# Power_MCU.net
KiCad netlist of a schematic drawn in Altium Designer
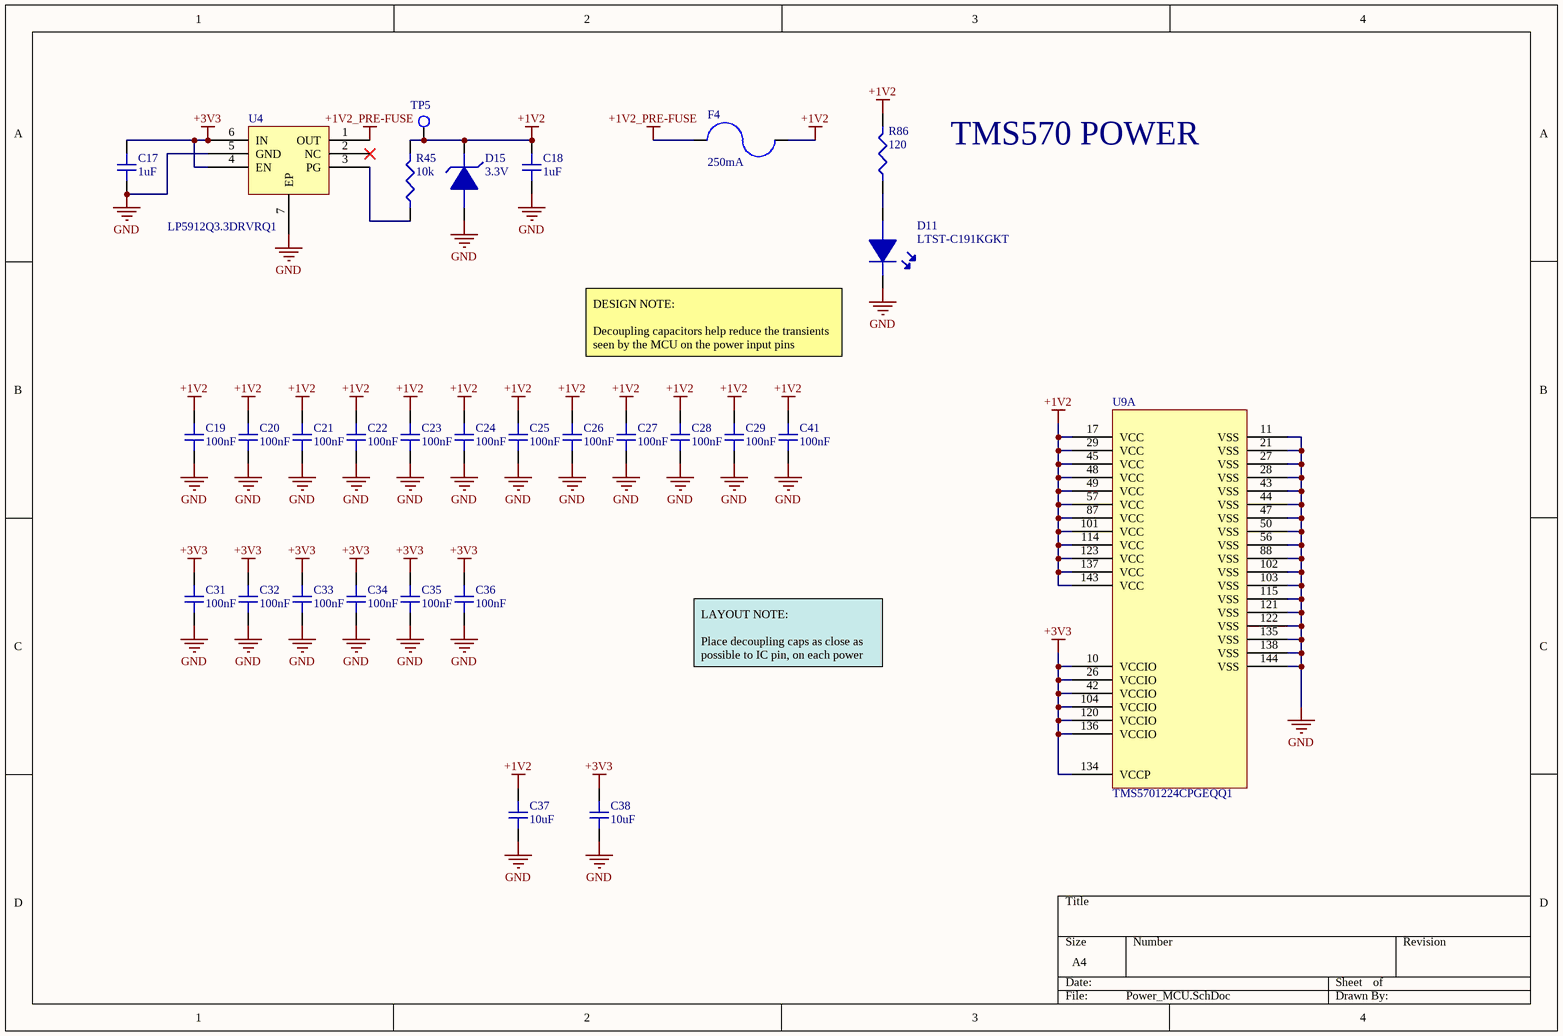
[diagram p0: Power_MCU.SchDoc]

(export (version "E")
  (design (tool "Eeschema 10.0.6"))
  (components
    (comp (ref "C17")
      (value "1uF")
      (footprint "C0805")
      (description "CAP CER 1UF 10V X7R 0805")
      (fields
        (field (name "MANUFACTURER") "Kyocera AVX")
        (field (name "MANUFACTURER PART NUMBER") "0805ZC105KAT2A")
      )
      (libsource (lib "PHANTOM_LIBRARY") (part "0805ZC105KAT2A"))
    )
    (comp (ref "C18")
      (value "1uF")
      (footprint "C0805")
      (description "CAP CER 1UF 10V X7R 0805")
      (fields
        (field (name "MANUFACTURER") "Kyocera AVX")
        (field (name "MANUFACTURER PART NUMBER") "0805ZC105KAT2A")
      )
      (libsource (lib "PHANTOM_LIBRARY") (part "0805ZC105KAT2A"))
    )
    (comp (ref "C19")
      (value "100nF")
      (footprint "PHANTOM_FOOTPRINTS:C0805")
      (description "CAP MLCC 100nF 10Volts U2J 5%")
      (fields
        (field (name "MANUFACTURER") "Murata")
        (field (name "MANUFACTURER PART NUMBER") "GRM21B7U1A104JA01L")
      )
      (libsource (lib "PHANTOM_LIBRARY") (part "GRM21B7U1A104JA01L"))
    )
    (comp (ref "C20")
      (value "100nF")
      (footprint "PHANTOM_FOOTPRINTS:C0805")
      (description "CAP MLCC 100nF 10Volts U2J 5%")
      (fields
        (field (name "MANUFACTURER") "Murata")
        (field (name "MANUFACTURER PART NUMBER") "GRM21B7U1A104JA01L")
      )
      (libsource (lib "PHANTOM_LIBRARY") (part "GRM21B7U1A104JA01L"))
    )
    (comp (ref "C21")
      (value "100nF")
      (footprint "PHANTOM_FOOTPRINTS:C0805")
      (description "CAP MLCC 100nF 10Volts U2J 5%")
      (fields
        (field (name "MANUFACTURER") "Murata")
        (field (name "MANUFACTURER PART NUMBER") "GRM21B7U1A104JA01L")
      )
      (libsource (lib "PHANTOM_LIBRARY") (part "GRM21B7U1A104JA01L"))
    )
    (comp (ref "C22")
      (value "100nF")
      (footprint "PHANTOM_FOOTPRINTS:C0805")
      (description "CAP MLCC 100nF 10Volts U2J 5%")
      (fields
        (field (name "MANUFACTURER") "Murata")
        (field (name "MANUFACTURER PART NUMBER") "GRM21B7U1A104JA01L")
      )
      (libsource (lib "PHANTOM_LIBRARY") (part "GRM21B7U1A104JA01L"))
    )
    (comp (ref "C23")
      (value "100nF")
      (footprint "PHANTOM_FOOTPRINTS:C0805")
      (description "CAP MLCC 100nF 10Volts U2J 5%")
      (fields
        (field (name "MANUFACTURER") "Murata")
        (field (name "MANUFACTURER PART NUMBER") "GRM21B7U1A104JA01L")
      )
      (libsource (lib "PHANTOM_LIBRARY") (part "GRM21B7U1A104JA01L"))
    )
    (comp (ref "C24")
      (value "100nF")
      (footprint "PHANTOM_FOOTPRINTS:C0805")
      (description "CAP MLCC 100nF 10Volts U2J 5%")
      (fields
        (field (name "MANUFACTURER") "Murata")
        (field (name "MANUFACTURER PART NUMBER") "GRM21B7U1A104JA01L")
      )
      (libsource (lib "PHANTOM_LIBRARY") (part "GRM21B7U1A104JA01L"))
    )
    (comp (ref "C25")
      (value "100nF")
      (footprint "PHANTOM_FOOTPRINTS:C0805")
      (description "CAP MLCC 100nF 10Volts U2J 5%")
      (fields
        (field (name "MANUFACTURER") "Murata")
        (field (name "MANUFACTURER PART NUMBER") "GRM21B7U1A104JA01L")
      )
      (libsource (lib "PHANTOM_LIBRARY") (part "GRM21B7U1A104JA01L"))
    )
    (comp (ref "C26")
      (value "100nF")
      (footprint "PHANTOM_FOOTPRINTS:C0805")
      (description "CAP MLCC 100nF 10Volts U2J 5%")
      (fields
        (field (name "MANUFACTURER") "Murata")
        (field (name "MANUFACTURER PART NUMBER") "GRM21B7U1A104JA01L")
      )
      (libsource (lib "PHANTOM_LIBRARY") (part "GRM21B7U1A104JA01L"))
    )
    (comp (ref "C27")
      (value "100nF")
      (footprint "PHANTOM_FOOTPRINTS:C0805")
      (description "CAP MLCC 100nF 10Volts U2J 5%")
      (fields
        (field (name "MANUFACTURER") "Murata")
        (field (name "MANUFACTURER PART NUMBER") "GRM21B7U1A104JA01L")
      )
      (libsource (lib "PHANTOM_LIBRARY") (part "GRM21B7U1A104JA01L"))
    )
    (comp (ref "C28")
      (value "100nF")
      (footprint "PHANTOM_FOOTPRINTS:C0805")
      (description "CAP MLCC 100nF 10Volts U2J 5%")
      (fields
        (field (name "MANUFACTURER") "Murata")
        (field (name "MANUFACTURER PART NUMBER") "GRM21B7U1A104JA01L")
      )
      (libsource (lib "PHANTOM_LIBRARY") (part "GRM21B7U1A104JA01L"))
    )
    (comp (ref "C29")
      (value "100nF")
      (footprint "PHANTOM_FOOTPRINTS:C0805")
      (description "CAP MLCC 100nF 10Volts U2J 5%")
      (fields
        (field (name "MANUFACTURER") "Murata")
        (field (name "MANUFACTURER PART NUMBER") "GRM21B7U1A104JA01L")
      )
      (libsource (lib "PHANTOM_LIBRARY") (part "GRM21B7U1A104JA01L"))
    )
    (comp (ref "C31")
      (value "100nF")
      (footprint "PHANTOM_FOOTPRINTS:C0805")
      (description "CAP MLCC 100nF 10Volts U2J 5%")
      (fields
        (field (name "MANUFACTURER") "Murata")
        (field (name "MANUFACTURER PART NUMBER") "GRM21B7U1A104JA01L")
      )
      (libsource (lib "PHANTOM_LIBRARY") (part "GRM21B7U1A104JA01L"))
    )
    (comp (ref "C32")
      (value "100nF")
      (footprint "PHANTOM_FOOTPRINTS:C0805")
      (description "CAP MLCC 100nF 10Volts U2J 5%")
      (fields
        (field (name "MANUFACTURER") "Murata")
        (field (name "MANUFACTURER PART NUMBER") "GRM21B7U1A104JA01L")
      )
      (libsource (lib "PHANTOM_LIBRARY") (part "GRM21B7U1A104JA01L"))
    )
    (comp (ref "C33")
      (value "100nF")
      (footprint "PHANTOM_FOOTPRINTS:C0805")
      (description "CAP MLCC 100nF 10Volts U2J 5%")
      (fields
        (field (name "MANUFACTURER") "Murata")
        (field (name "MANUFACTURER PART NUMBER") "GRM21B7U1A104JA01L")
      )
      (libsource (lib "PHANTOM_LIBRARY") (part "GRM21B7U1A104JA01L"))
    )
    (comp (ref "C34")
      (value "100nF")
      (footprint "PHANTOM_FOOTPRINTS:C0805")
      (description "CAP MLCC 100nF 10Volts U2J 5%")
      (fields
        (field (name "MANUFACTURER") "Murata")
        (field (name "MANUFACTURER PART NUMBER") "GRM21B7U1A104JA01L")
      )
      (libsource (lib "PHANTOM_LIBRARY") (part "GRM21B7U1A104JA01L"))
    )
    (comp (ref "C35")
      (value "100nF")
      (footprint "PHANTOM_FOOTPRINTS:C0805")
      (description "CAP MLCC 100nF 10Volts U2J 5%")
      (fields
        (field (name "MANUFACTURER") "Murata")
        (field (name "MANUFACTURER PART NUMBER") "GRM21B7U1A104JA01L")
      )
      (libsource (lib "PHANTOM_LIBRARY") (part "GRM21B7U1A104JA01L"))
    )
    (comp (ref "C36")
      (value "100nF")
      (footprint "PHANTOM_FOOTPRINTS:C0805")
      (description "CAP MLCC 100nF 10Volts U2J 5%")
      (fields
        (field (name "MANUFACTURER") "Murata")
        (field (name "MANUFACTURER PART NUMBER") "GRM21B7U1A104JA01L")
      )
      (libsource (lib "PHANTOM_LIBRARY") (part "GRM21B7U1A104JA01L"))
    )
    (comp (ref "C37")
      (value "10uF")
      (footprint "TANT_10u")
      (fields
        (field (name "MANUFACTURER") "Kyocera AVX")
        (field (name "MANUFACTURER PART NUMBER") "F381A106MMA")
        (field (name "TOLERANCE") "20%")
      )
      (libsource (lib "PHANTOM_LIBRARY") (part "F381A106MMA"))
    )
    (comp (ref "C38")
      (value "10uF")
      (footprint "TANT_10u")
      (fields
        (field (name "MANUFACTURER") "Kyocera AVX")
        (field (name "MANUFACTURER PART NUMBER") "F381A106MMA")
        (field (name "TOLERANCE") "20%")
      )
      (libsource (lib "PHANTOM_LIBRARY") (part "F381A106MMA"))
    )
    (comp (ref "C41")
      (value "100nF")
      (footprint "PHANTOM_FOOTPRINTS:C0805")
      (description "CAP MLCC 100nF 10Volts U2J 5%")
      (fields
        (field (name "MANUFACTURER") "Murata")
        (field (name "MANUFACTURER PART NUMBER") "GRM21B7U1A104JA01L")
      )
      (libsource (lib "PHANTOM_LIBRARY") (part "GRM21B7U1A104JA01L"))
    )
    (comp (ref "D11")
      (value "LTST-C191KGKT")
      (footprint "LED_0603")
      (description "LED GREEN CLEAR 0603 SMD")
      (fields (field (name "MANUFACTURER") "Vishay Lite-On"))
      (libsource (lib "PHANTOM_LIBRARY") (part "LTST-C191KGKT"))
    )
    (comp (ref "D15")
      (value "3.3V")
      (footprint "DIODE_TVS")
      (description "DIODE ZENER 3.3V 1.5W SMA")
      (fields
        (field (name "MANUFACTURER") "ON Semiconductor")
        (field (name "MANUFACTURER PART NUMBER") "1SMA5913BT3G")
      )
      (libsource (lib "PHANTOM_LIBRARY") (part "1SMA5913BT3G"))
    )
    (comp (ref "F4")
      (value "250mA")
      (footprint "FUSE_0603")
      (description "FUSE_0.25A SMD 0603 BOARD MNT 250MA 32VAC 63VDC")
      (fields (field (name "MANUFACTURER") "Bel") (field (name "MANUFACTURER PART NUMBER") "C2Q250"))
      (libsource (lib "PHANTOM_LIBRARY") (part "C2Q250"))
    )
    (comp (ref "R45")
      (value "10k")
      (footprint "R0805")
      (description "RES SMD 10K OHM 1% 1/8W 0805")
      (fields
        (field (name "MANUFACTURER") "Yageo Phycomp")
        (field (name "MANUFACTURER PART NUMBER") "RC0805FR-071KL")
      )
      (libsource (lib "PHANTOM_LIBRARY") (part "RC0805FR-071KL"))
    )
    (comp (ref "R86")
      (value "120")
      (footprint "R0805")
      (description "RES SMD 120 OHM 1% 1/8W 0805")
      (fields
        (field (name "MANUFACTURER") "Yageo")
        (field (name "MANUFACTURER PART NUMBER") "RC0805FR-07120RL")
      )
      (libsource (lib "PHANTOM_LIBRARY") (part "RC0805FR-07120RL"))
    )
    (comp (ref "TP5")
      (value "5015")
      (footprint "TP_HOOK")
      (description "TEST POINT, PCB, SMT")
      (fields (field (name "MANUFACTURER") "Keystone Electronics"))
      (libsource (lib "PHANTOM_LIBRARY") (part "5015"))
    )
    (comp (ref "U4")
      (value "LP5912Q3.3DRVRQ1")
      (footprint "WSON")
      (description "LDO_1V2 REG 3.3V INPUT 1V2 OUTPUT 0.5A")
      (fields (field (name "MANUFACTURER") "Texas Instruments"))
      (libsource (lib "PHANTOM_LIBRARY") (part "LP5912Q3.3DRVRQ1"))
    )
    (comp (ref "U9")
      (value "TMS5701224CPGEQQ1")
      (footprint "LQFP-144")
      (description "ARM CORTEX R4 LOCK STEP HERCULES MCU")
      (fields (field (name "MANUFACTURER") "Texas Instruments"))
      (libsource (lib "PHANTOM_LIBRARY") (part "TMS5701224CPGEQQ1"))
    )
  )
  (nets
    (net (code "1") (name "+1V2") (class "Default")
      (node (ref "C18") (pin "2") (pinfunction "2_2") (pintype "passive"))
      (node (ref "C19") (pin "2") (pinfunction "2_2") (pintype "passive"))
      (node (ref "C20") (pin "2") (pinfunction "2_2") (pintype "passive"))
      (node (ref "C21") (pin "2") (pinfunction "2_2") (pintype "passive"))
      (node (ref "C22") (pin "2") (pinfunction "2_2") (pintype "passive"))
      (node (ref "C23") (pin "2") (pinfunction "2_2") (pintype "passive"))
      (node (ref "C24") (pin "2") (pinfunction "2_2") (pintype "passive"))
      (node (ref "C25") (pin "2") (pinfunction "2_2") (pintype "passive"))
      (node (ref "C26") (pin "2") (pinfunction "2_2") (pintype "passive"))
      (node (ref "C27") (pin "2") (pinfunction "2_2") (pintype "passive"))
      (node (ref "C28") (pin "2") (pinfunction "2_2") (pintype "passive"))
      (node (ref "C29") (pin "2") (pinfunction "2_2") (pintype "passive"))
      (node (ref "C37") (pin "1") (pinfunction "1_1") (pintype "passive"))
      (node (ref "C41") (pin "2") (pinfunction "2_2") (pintype "passive"))
      (node (ref "D15") (pin "1") (pinfunction "1_1") (pintype "passive"))
      (node (ref "F4") (pin "2") (pinfunction "2_2") (pintype "passive"))
      (node (ref "R45") (pin "2") (pinfunction "2_2") (pintype "passive"))
      (node (ref "R86") (pin "2") (pinfunction "2_2") (pintype "passive"))
      (node (ref "TP5") (pin "1") (pinfunction "1_1") (pintype "passive"))
      (node (ref "U9") (pin "101") (pinfunction "VCC_101") (pintype "passive"))
      (node (ref "U9") (pin "114") (pinfunction "VCC_114") (pintype "passive"))
      (node (ref "U9") (pin "123") (pinfunction "VCC_123") (pintype "passive"))
      (node (ref "U9") (pin "137") (pinfunction "VCC_137") (pintype "passive"))
      (node (ref "U9") (pin "143") (pinfunction "VCC_143") (pintype "passive"))
      (node (ref "U9") (pin "17") (pinfunction "VCC_17") (pintype "passive"))
      (node (ref "U9") (pin "29") (pinfunction "VCC_29") (pintype "passive"))
      (node (ref "U9") (pin "45") (pinfunction "VCC_45") (pintype "passive"))
      (node (ref "U9") (pin "48") (pinfunction "VCC_48") (pintype "passive"))
      (node (ref "U9") (pin "49") (pinfunction "VCC_49") (pintype "passive"))
      (node (ref "U9") (pin "57") (pinfunction "VCC_57") (pintype "passive"))
      (node (ref "U9") (pin "87") (pinfunction "VCC_87") (pintype "passive"))
    )
    (net (code "2") (name "+1V2_PRE-FUSE") (class "Default")
      (node (ref "F4") (pin "1") (pinfunction "1_1") (pintype "passive"))
      (node (ref "U4") (pin "1") (pinfunction "OUT_1") (pintype "passive"))
    )
    (net (code "3") (name "+3V3") (class "Default")
      (node (ref "C17") (pin "2") (pinfunction "2_2") (pintype "passive"))
      (node (ref "C31") (pin "2") (pinfunction "2_2") (pintype "passive"))
      (node (ref "C32") (pin "2") (pinfunction "2_2") (pintype "passive"))
      (node (ref "C33") (pin "2") (pinfunction "2_2") (pintype "passive"))
      (node (ref "C34") (pin "2") (pinfunction "2_2") (pintype "passive"))
      (node (ref "C35") (pin "2") (pinfunction "2_2") (pintype "passive"))
      (node (ref "C36") (pin "2") (pinfunction "2_2") (pintype "passive"))
      (node (ref "C38") (pin "1") (pinfunction "1_1") (pintype "passive"))
      (node (ref "U4") (pin "4") (pinfunction "EN_4") (pintype "passive"))
      (node (ref "U4") (pin "6") (pinfunction "IN_6") (pintype "passive"))
      (node (ref "U9") (pin "10") (pinfunction "VCCIO_10") (pintype "passive"))
      (node (ref "U9") (pin "104") (pinfunction "VCCIO_104") (pintype "passive"))
      (node (ref "U9") (pin "120") (pinfunction "VCCIO_120") (pintype "passive"))
      (node (ref "U9") (pin "134") (pinfunction "VCCP_134") (pintype "passive"))
      (node (ref "U9") (pin "136") (pinfunction "VCCIO_136") (pintype "passive"))
      (node (ref "U9") (pin "26") (pinfunction "VCCIO_26") (pintype "passive"))
      (node (ref "U9") (pin "42") (pinfunction "VCCIO_42") (pintype "passive"))
    )
    (net (code "4") (name "GND") (class "Default")
      (node (ref "C17") (pin "1") (pinfunction "1_1") (pintype "passive"))
      (node (ref "C18") (pin "1") (pinfunction "1_1") (pintype "passive"))
      (node (ref "C19") (pin "1") (pinfunction "1_1") (pintype "passive"))
      (node (ref "C20") (pin "1") (pinfunction "1_1") (pintype "passive"))
      (node (ref "C21") (pin "1") (pinfunction "1_1") (pintype "passive"))
      (node (ref "C22") (pin "1") (pinfunction "1_1") (pintype "passive"))
      (node (ref "C23") (pin "1") (pinfunction "1_1") (pintype "passive"))
      (node (ref "C24") (pin "1") (pinfunction "1_1") (pintype "passive"))
      (node (ref "C25") (pin "1") (pinfunction "1_1") (pintype "passive"))
      (node (ref "C26") (pin "1") (pinfunction "1_1") (pintype "passive"))
      (node (ref "C27") (pin "1") (pinfunction "1_1") (pintype "passive"))
      (node (ref "C28") (pin "1") (pinfunction "1_1") (pintype "passive"))
      (node (ref "C29") (pin "1") (pinfunction "1_1") (pintype "passive"))
      (node (ref "C31") (pin "1") (pinfunction "1_1") (pintype "passive"))
      (node (ref "C32") (pin "1") (pinfunction "1_1") (pintype "passive"))
      (node (ref "C33") (pin "1") (pinfunction "1_1") (pintype "passive"))
      (node (ref "C34") (pin "1") (pinfunction "1_1") (pintype "passive"))
      (node (ref "C35") (pin "1") (pinfunction "1_1") (pintype "passive"))
      (node (ref "C36") (pin "1") (pinfunction "1_1") (pintype "passive"))
      (node (ref "C37") (pin "2") (pinfunction "2_2") (pintype "passive"))
      (node (ref "C38") (pin "2") (pinfunction "2_2") (pintype "passive"))
      (node (ref "C41") (pin "1") (pinfunction "1_1") (pintype "passive"))
      (node (ref "D11") (pin "2") (pinfunction "2_2") (pintype "passive"))
      (node (ref "D15") (pin "2") (pinfunction "2_2") (pintype "passive"))
      (node (ref "U4") (pin "5") (pinfunction "GND_5") (pintype "passive"))
      (node (ref "U4") (pin "7") (pinfunction "EP_7") (pintype "passive"))
      (node (ref "U9") (pin "102") (pinfunction "VSS_102") (pintype "passive"))
      (node (ref "U9") (pin "103") (pinfunction "VSS_103") (pintype "passive"))
      (node (ref "U9") (pin "11") (pinfunction "VSS_11") (pintype "passive"))
      (node (ref "U9") (pin "115") (pinfunction "VSS_115") (pintype "passive"))
      (node (ref "U9") (pin "121") (pinfunction "VSS_121") (pintype "passive"))
      (node (ref "U9") (pin "122") (pinfunction "VSS_122") (pintype "passive"))
      (node (ref "U9") (pin "135") (pinfunction "VSS_135") (pintype "passive"))
      (node (ref "U9") (pin "138") (pinfunction "VSS_138") (pintype "passive"))
      (node (ref "U9") (pin "144") (pinfunction "VSS_144") (pintype "passive"))
      (node (ref "U9") (pin "21") (pinfunction "VSS_21") (pintype "passive"))
      (node (ref "U9") (pin "27") (pinfunction "VSS_27") (pintype "passive"))
      (node (ref "U9") (pin "28") (pinfunction "VSS_28") (pintype "passive"))
      (node (ref "U9") (pin "43") (pinfunction "VSS_43") (pintype "passive"))
      (node (ref "U9") (pin "44") (pinfunction "VSS_44") (pintype "passive"))
      (node (ref "U9") (pin "47") (pinfunction "VSS_47") (pintype "passive"))
      (node (ref "U9") (pin "50") (pinfunction "VSS_50") (pintype "passive"))
      (node (ref "U9") (pin "56") (pinfunction "VSS_56") (pintype "passive"))
      (node (ref "U9") (pin "88") (pinfunction "VSS_88") (pintype "passive"))
    )
    (net (code "5") (name "Net-(D11-Pad1)") (class "Default")
      (node (ref "D11") (pin "1") (pinfunction "1_1") (pintype "passive"))
      (node (ref "R86") (pin "1") (pinfunction "1_1") (pintype "passive"))
    )
    (net (code "6") (name "Net-(U4-PG)") (class "Default")
      (node (ref "R45") (pin "1") (pinfunction "1_1") (pintype "passive"))
      (node (ref "U4") (pin "3") (pinfunction "PG_3") (pintype "passive"))
    )
    (net (code "7") (name "unconnected-(U4-NC-Pad2)") (class "Default")
      (node (ref "U4") (pin "2") (pinfunction "NC_2") (pintype "passive+no_connect"))
    )
  )
)
